# PAW4_NOMAG_Cheesecake-Blueberry-LSM6DSV_.net
KiCad netlist of a schematic drawn in EasyEDA Pro
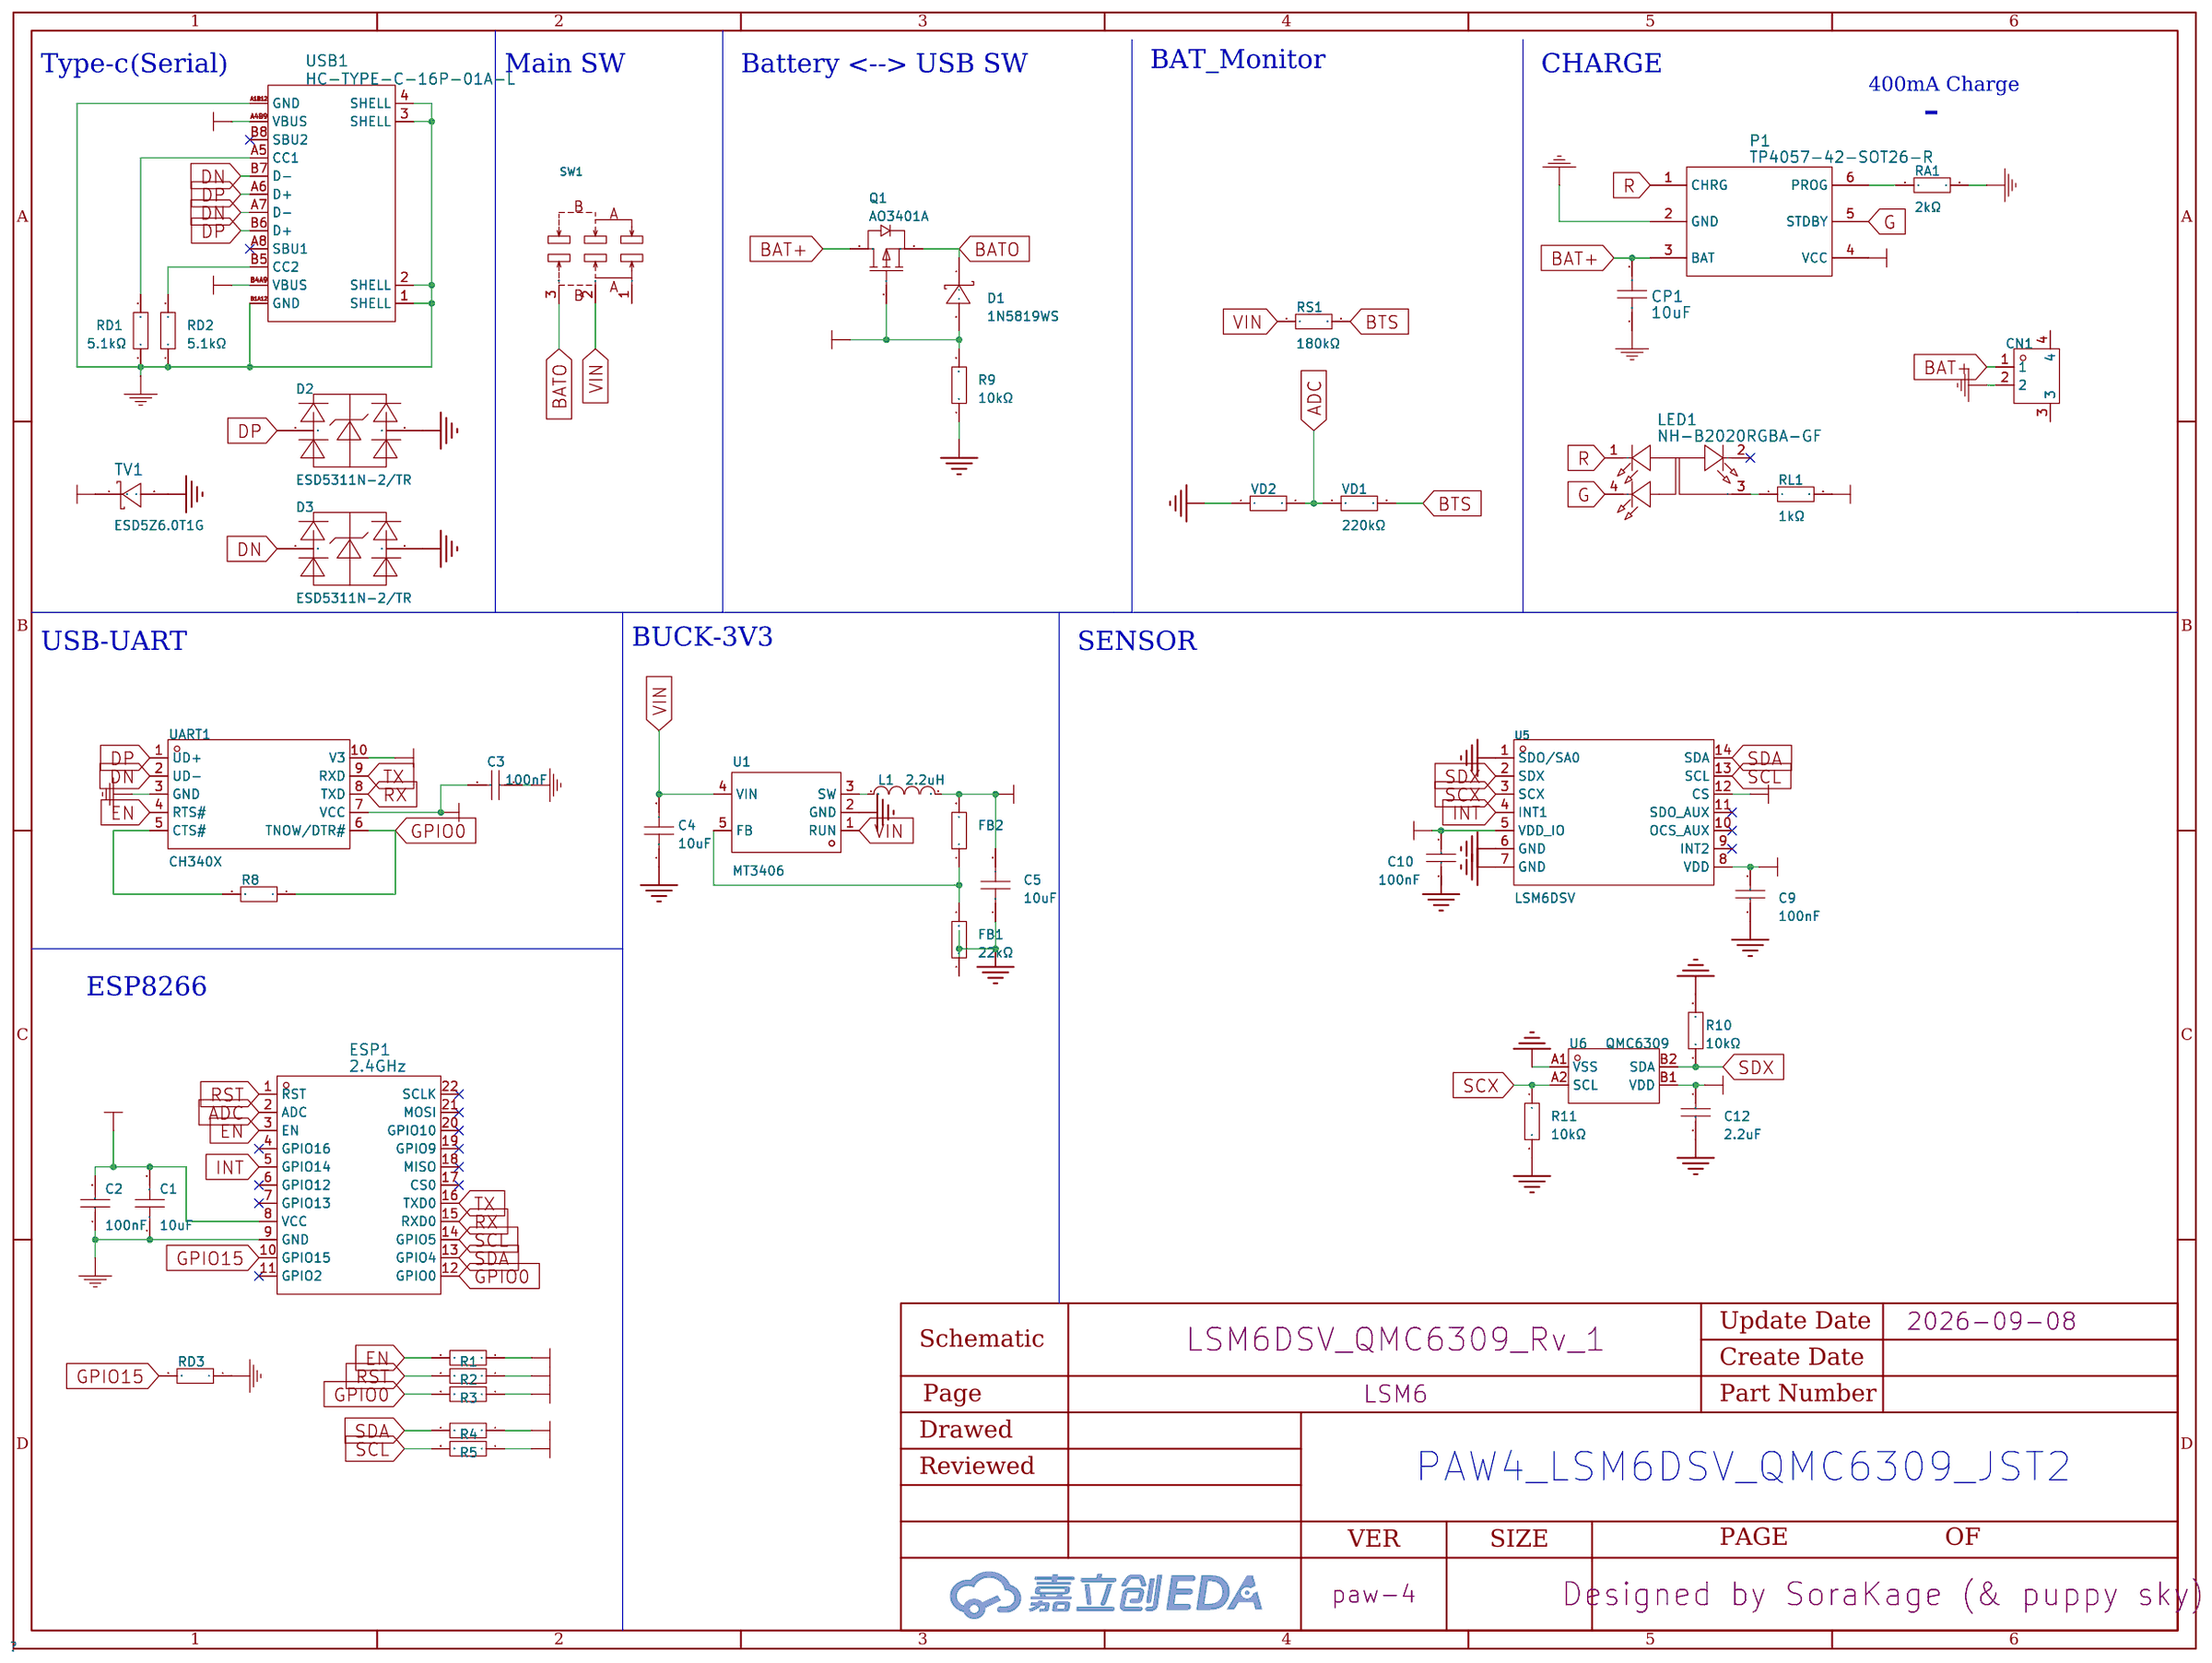
[diagram p0: schematic sheet]

(export (version "E")
  (design (tool "Eeschema 10.0.6"))
  (components
    (comp (ref "C1")
      (value "10uF")
      (footprint "easyedapro:C0402")
      (description "Capacitance:10uF Tolerance:±10% Tolerance:±10% Voltage Rating:10V Temperature Coefficient:X5R")
      (fields
        (field (name "Manufacturer Part") "CL10A106KP8NNNC")
        (field (name "Manufacturer") "SAMSUNG(三星)")
      )
      (libsource (lib "easyedapro") (part "CL05A105KA5NQNC"))
    )
    (comp (ref "C2")
      (value "100nF")
      (footprint "easyedapro:C0402")
      (description "容值:100nF;精度:±10%;额定电压:16V;材质(温度系数):X7R;")
      (fields
        (field (name "Manufacturer Part") "CL05B104KO5NNNC")
        (field (name "Manufacturer") "SAMSUNG(三星)")
      )
      (libsource (lib "easyedapro") (part "CL05B104KO5NNNC"))
    )
    (comp (ref "C3")
      (value "100nF")
      (footprint "easyedapro:C0402")
      (description "容值:100nF;精度:±10%;额定电压:16V;材质(温度系数):X7R;")
      (fields
        (field (name "Manufacturer Part") "CL05B104KO5NNNC")
        (field (name "Manufacturer") "SAMSUNG(三星)")
      )
      (libsource (lib "easyedapro") (part "CL05B104KO5NNNC"))
    )
    (comp (ref "C4")
      (value "10uF")
      (footprint "easyedapro:C0603")
      (description "容值:10uF;精度:±10%;额定电压:10V;材质(温度系数):X5R;")
      (fields
        (field (name "Manufacturer Part") "CL10A106KP8NNNC")
        (field (name "Manufacturer") "SAMSUNG(三星)")
      )
      (libsource (lib "easyedapro") (part "CL10A106KP8NNNC"))
    )
    (comp (ref "C5")
      (value "10uF")
      (footprint "easyedapro:C0603")
      (description "容值:10uF;精度:±10%;额定电压:10V;材质(温度系数):X5R;")
      (fields
        (field (name "Manufacturer Part") "CL10A106KP8NNNC")
        (field (name "Manufacturer") "SAMSUNG(三星)")
      )
      (libsource (lib "easyedapro") (part "CL10A106KP8NNNC"))
    )
    (comp (ref "C9")
      (value "100nF")
      (footprint "easyedapro:C0402")
      (description "容值:100nF;精度:±10%;额定电压:16V;材质(温度系数):X7R;")
      (fields
        (field (name "Manufacturer Part") "CL05B104KO5NNNC")
        (field (name "Manufacturer") "SAMSUNG(三星)")
      )
      (libsource (lib "easyedapro") (part "CL05B104KO5NNNC"))
    )
    (comp (ref "C10")
      (value "100nF")
      (footprint "easyedapro:C0402")
      (description "容值:100nF;精度:±10%;额定电压:16V;材质(温度系数):X7R;")
      (fields
        (field (name "Manufacturer Part") "CL05B104KO5NNNC")
        (field (name "Manufacturer") "SAMSUNG(三星)")
      )
      (libsource (lib "easyedapro") (part "CL05B104KO5NNNC"))
    )
    (comp (ref "C12")
      (value "2.2uF")
      (footprint "easyedapro:C0402")
      (description "Capacitance:2.2uF Tolerance:±10% Tolerance:±10% Voltage Rating:6.3V Temperature Coefficient:X5R")
      (fields (field (name "Manufacturer Part") "0402X225K6R3NT") (field (name "Manufacturer") "FH(风华)"))
      (libsource (lib "easyedapro") (part "CL05B104KO5NNNC"))
    )
    (comp (ref "CN1")
      (value "S2B-PH-SM4-TB(LF)(SN)")
      (footprint "easyedapro:CONN-SMD_P2.00_S2B-PH-SM4-TB-LF-SN")
      (fields (field (name "Manufacturer") "JST"))
      (libsource (lib "easyedapro") (part "S2B-PH-SM4-TB(LF)(SN)"))
    )
    (comp (ref "CP1")
      (value "10uF")
      (footprint "easyedapro:C0603")
      (fields
        (field (name "Manufacturer Part") "CL10A106KP8NNNC")
        (field (name "Manufacturer") "SAMSUNG(三星)")
      )
      (libsource (lib "easyedapro") (part "10uF"))
    )
    (comp (ref "D1")
      (value "1N5819WS")
      (footprint "easyedapro:SOD-323_L1.8-W1.3-LS2.5-RD")
      (description "直流反向耐压(Vr):40V;平均整流电流(Io):1A;正向压降(Vf):600mV@1A;")
      (fields (field (name "Manufacturer") "Hottech(合科泰)"))
      (libsource (lib "easyedapro") (part "1N5819WS"))
    )
    (comp (ref "D2")
      (value "ESD5311N-2/TR")
      (footprint "easyedapro:X1-DFN1006-2_L1.0-W0.6_ESD5311N-2-TR")
      (fields (field (name "Manufacturer") "WILLSEMI(韦尔)"))
      (libsource (lib "easyedapro") (part "ESD5311N-2/TR"))
    )
    (comp (ref "D3")
      (value "ESD5311N-2/TR")
      (footprint "easyedapro:X1-DFN1006-2_L1.0-W0.6_ESD5311N-2-TR")
      (fields (field (name "Manufacturer") "WILLSEMI(韦尔)"))
      (libsource (lib "easyedapro") (part "ESD5311N-2/TR"))
    )
    (comp (ref "ESP1")
      (value "2.4GHz")
      (description "核心处理器:ESP8266芯片;频率:2.4GHz;天线形式:板载PCB天线;发射功率:16dBm;接收灵敏度:-90dBm;")
      (fields
        (field (name "Manufacturer Part") "ESP-12F(ESP8266MOD)")
        (field (name "Manufacturer") "Ai-Thinker(安信可)")
      )
      (libsource (lib "easyedapro") (part "ESP-12F(ESP8266MOD)"))
    )
    (comp (ref "FB1")
      (value "22kΩ")
      (footprint "easyedapro:R0402")
      (description "电阻类型:厚膜电阻;阻值:22kΩ;精度:±1%;功率:62.5mW;")
      (fields
        (field (name "Manufacturer Part") "0402WGF2202TCE")
        (field (name "Manufacturer") "UNI-ROYAL(厚声)")
      )
      (libsource (lib "easyedapro") (part "0402WGF2202TCE"))
    )
    (comp (ref "FB2")
      (value "100kΩ")
      (footprint "easyedapro:R0402")
      (fields
        (field (name "Manufacturer Part") "0402WGF1003TCE")
        (field (name "Manufacturer") "UNI-ROYAL(厚声)")
      )
      (libsource (lib "easyedapro") (part "0402WGF1003TCE"))
    )
    (comp (ref "L1")
      (value "2.2uH")
      (footprint "easyedapro:IND-SMD_L2.5-W2.0_YXMBL252010P")
      (description "类型:一体成型电感;电感值:2.2uH;精度:±20%;额定电流:2.1A;饱和电流(Isat):3A;")
      (fields (field (name "Manufacturer Part") "APH252010T2R2M") (field (name "Manufacturer") "APV(爱普微)"))
      (libsource (lib "easyedapro") (part "APH252010T2R2M"))
    )
    (comp (ref "LED1")
      (value "NH-B2020RGBA-GF")
      (footprint "easyedapro:LED-ARRAY-SMD_4P-L2.1-W2.1-TL_NH-B2020RGBA")
      (fields (field (name "Manufacturer") "国星光电"))
      (libsource (lib "easyedapro") (part "NH-B2020RGBA-GF"))
    )
    (comp (ref "P1")
      (value "TP4057-42-SOT26-R")
      (footprint "easyedapro:SOT-23-6_L2.9-W1.6-P0.95-LS2.8-BL")
      (fields (field (name "Manufacturer") "TOPPOWER(南京拓微)"))
      (libsource (lib "easyedapro") (part "TP4057"))
    )
    (comp (ref "Q1")
      (value "AO3401A")
      (footprint "easyedapro:SOT-23_L2.9-W1.3-P1.90-LS2.4-BR")
      (description "类型:P沟道;漏源电压(Vdss):30V;连续漏极电流(Id):4A;功率(Pd):1.4W;导通电阻(RDS(on)@Vgs,Id):44mΩ@10V,4.3A;")
      (fields (field (name "Manufacturer") "AOS"))
      (libsource (lib "easyedapro") (part "AO3401A"))
    )
    (comp (ref "R1")
      (value "4.7kΩ")
      (footprint "easyedapro:R0402")
      (fields
        (field (name "Manufacturer Part") "0402WGF4701TCE")
        (field (name "Manufacturer") "UNI-ROYAL(厚声)")
      )
      (libsource (lib "easyedapro") (part "0402WGF4701TCE"))
    )
    (comp (ref "R2")
      (value "4.7kΩ")
      (footprint "easyedapro:R0402")
      (fields
        (field (name "Manufacturer Part") "0402WGF4701TCE")
        (field (name "Manufacturer") "UNI-ROYAL(厚声)")
      )
      (libsource (lib "easyedapro") (part "0402WGF4701TCE"))
    )
    (comp (ref "R3")
      (value "4.7kΩ")
      (footprint "easyedapro:R0402")
      (fields
        (field (name "Manufacturer Part") "0402WGF4701TCE")
        (field (name "Manufacturer") "UNI-ROYAL(厚声)")
      )
      (libsource (lib "easyedapro") (part "0402WGF4701TCE"))
    )
    (comp (ref "R4")
      (value "4.7kΩ")
      (footprint "easyedapro:R0402")
      (fields
        (field (name "Manufacturer Part") "0402WGF4701TCE")
        (field (name "Manufacturer") "UNI-ROYAL(厚声)")
      )
      (libsource (lib "easyedapro") (part "0402WGF4701TCE"))
    )
    (comp (ref "R5")
      (value "4.7kΩ")
      (footprint "easyedapro:R0402")
      (fields
        (field (name "Manufacturer Part") "0402WGF4701TCE")
        (field (name "Manufacturer") "UNI-ROYAL(厚声)")
      )
      (libsource (lib "easyedapro") (part "0402WGF4701TCE"))
    )
    (comp (ref "R8")
      (value "4.7kΩ")
      (footprint "easyedapro:R0402")
      (fields
        (field (name "Manufacturer Part") "0402WGF4701TCE")
        (field (name "Manufacturer") "UNI-ROYAL(厚声)")
      )
      (libsource (lib "easyedapro") (part "0402WGF4701TCE"))
    )
    (comp (ref "R9")
      (value "10kΩ")
      (footprint "easyedapro:R0402")
      (description "电阻类型:厚膜电阻;阻值:10kΩ;精度:±1%;功率:62.5mW;")
      (fields
        (field (name "Manufacturer Part") "0402WGF1002TCE")
        (field (name "Manufacturer") "UNI-ROYAL(厚声)")
      )
      (libsource (lib "easyedapro") (part "0402WGF1002TCE"))
    )
    (comp (ref "R10")
      (value "10kΩ")
      (footprint "easyedapro:R0402")
      (description "电阻类型:厚膜电阻;阻值:10kΩ;精度:±1%;功率:62.5mW;")
      (fields
        (field (name "Manufacturer Part") "0402WGF1002TCE")
        (field (name "Manufacturer") "UNI-ROYAL(厚声)")
      )
      (libsource (lib "easyedapro") (part "0402WGF1002TCE"))
    )
    (comp (ref "R11")
      (value "10kΩ")
      (footprint "easyedapro:R0402")
      (description "电阻类型:厚膜电阻;阻值:10kΩ;精度:±1%;功率:62.5mW;")
      (fields
        (field (name "Manufacturer Part") "0402WGF1002TCE")
        (field (name "Manufacturer") "UNI-ROYAL(厚声)")
      )
      (libsource (lib "easyedapro") (part "0402WGF1002TCE"))
    )
    (comp (ref "RA1")
      (value "2kΩ")
      (footprint "easyedapro:R0402")
      (description "电阻类型:厚膜电阻;阻值:2kΩ;精度:±1%;功率:62.5mW;")
      (fields
        (field (name "Manufacturer Part") "0402WGF2001TCE")
        (field (name "Manufacturer") "UNI-ROYAL(厚声)")
      )
      (libsource (lib "easyedapro") (part "0402WGF2001TCE"))
    )
    (comp (ref "RD1")
      (value "5.1kΩ")
      (footprint "easyedapro:R0402")
      (description "电阻类型:厚膜电阻;阻值:5.1kΩ;精度:±1%;功率:62.5mW;")
      (fields
        (field (name "Manufacturer Part") "0402WGF5101TCE")
        (field (name "Manufacturer") "UNI-ROYAL(厚声)")
      )
      (libsource (lib "easyedapro") (part "0402WGF5101TCE"))
    )
    (comp (ref "RD2")
      (value "5.1kΩ")
      (footprint "easyedapro:R0402")
      (description "电阻类型:厚膜电阻;阻值:5.1kΩ;精度:±1%;功率:62.5mW;")
      (fields
        (field (name "Manufacturer Part") "0402WGF5101TCE")
        (field (name "Manufacturer") "UNI-ROYAL(厚声)")
      )
      (libsource (lib "easyedapro") (part "0402WGF5101TCE"))
    )
    (comp (ref "RD3")
      (value "4.7kΩ")
      (footprint "easyedapro:R0402")
      (fields
        (field (name "Manufacturer Part") "0402WGF4701TCE")
        (field (name "Manufacturer") "UNI-ROYAL(厚声)")
      )
      (libsource (lib "easyedapro") (part "0402WGF4701TCE"))
    )
    (comp (ref "RL1")
      (value "1kΩ")
      (footprint "easyedapro:R0402")
      (description "电阻类型:厚膜电阻;阻值:1kΩ;精度:±1%;功率:62.5mW;")
      (fields
        (field (name "Manufacturer Part") "0402WGF1001TCE")
        (field (name "Manufacturer") "UNI-ROYAL(厚声)")
      )
      (libsource (lib "easyedapro") (part "0402WGF1001TCE"))
    )
    (comp (ref "RS1")
      (value "180kΩ")
      (footprint "easyedapro:R0402")
      (description "阻值:180kΩ;精度:±1%;功率:62.5mW;温度系数:±100ppm/°C;电阻类型:厚膜电阻;")
      (fields
        (field (name "Manufacturer Part") "0402WGF1803TCE")
        (field (name "Manufacturer") "UNI-ROYAL(厚声)")
      )
      (libsource (lib "easyedapro") (part "0402WGF1803TCE"))
    )
    (comp (ref "SW1")
      (value "K3-1280S-F1")
      (footprint "easyedapro:SW-SMD_K3-1280S-K1")
      (fields (field (name "Manufacturer") "韩国韩荣"))
      (libsource (lib "easyedapro") (part "K3-1280S-F2"))
    )
    (comp (ref "TV1")
      (value "ESD5Z6.0T1G")
      (footprint "easyedapro:SOD-523F_L1.2-W0.8-LS1.7-RD")
      (fields (field (name "Manufacturer") "onsemi(安森美)"))
      (libsource (lib "easyedapro") (part "ESD5Z6.0T1G"))
    )
    (comp (ref "U1")
      (value "MT3406")
      (footprint "easyedapro:SOT-23-5_L3.0-W1.7-P0.95-LS2.8-BR")
      (description "功能类型:降压型;同步整流:-;输出通道数:-;拓扑结构:-;输入电压:-;输出电流(最大值):-;开关频率:-;")
      (fields (field (name "Manufacturer") "西安航天民芯"))
      (libsource (lib "easyedapro") (part "M3406"))
    )
    (comp (ref "U5")
      (value "LSM6DSV")
      (footprint "easyedapro:LGA-14_L3.0-W2.5-P0.50-TL")
      (fields (field (name "Manufacturer") "ST(意法半导体)"))
      (libsource (lib "easyedapro") (part "LSM6DSVQTR"))
    )
    (comp (ref "U6")
      (value "QMC6309")
      (footprint "easyedapro:X1-WLB0808-4_L0.8-W0.8-P0.40-TL")
      (fields (field (name "Manufacturer") "QST(上海矽睿)"))
      (libsource (lib "easyedapro") (part "QMC6309"))
    )
    (comp (ref "UART1")
      (value "CH340X")
      (footprint "easyedapro:MSOP-10_L3.0-W3.0-P0.50-LS5.0-BL")
      (fields (field (name "Manufacturer") "WCH(南京沁恒)"))
      (libsource (lib "easyedapro") (part "CH340X"))
    )
    (comp (ref "USB1")
      (value "HC-TYPE-C-16P-01A-L")
      (footprint "easyedapro:USB-C-SMD_G-SWITCH_GT-USB-7010EN")
      (fields (field (name "Manufacturer") "HCTL(华灿天禄)"))
      (libsource (lib "easyedapro") (part "HC-TYPE-C-16P-01A-L"))
    )
    (comp (ref "VD1")
      (value "220kΩ")
      (footprint "easyedapro:R0402")
      (description "电阻类型:厚膜电阻;阻值:220kΩ;精度:±1%;功率:62.5mW;")
      (fields
        (field (name "Manufacturer Part") "0402WGF2203TCE")
        (field (name "Manufacturer") "UNI-ROYAL(厚声)")
      )
      (libsource (lib "easyedapro") (part "0402WGF2203TCE"))
    )
    (comp (ref "VD2")
      (value "100kΩ")
      (footprint "easyedapro:R0402")
      (fields
        (field (name "Manufacturer Part") "0402WGF1003TCE")
        (field (name "Manufacturer") "UNI-ROYAL(厚声)")
      )
      (libsource (lib "easyedapro") (part "0402WGF1003TCE"))
    )
  )
  (nets
    (net (code "1") (name "+5V") (class "Default")
      (node (ref "D1") (pin "2") (pinfunction "A_2") (pintype "unspecified"))
      (node (ref "P1") (pin "4") (pinfunction "VCC_4") (pintype "unspecified"))
      (node (ref "Q1") (pin "1") (pinfunction "G_1") (pintype "input"))
      (node (ref "R9") (pin "2") (pinfunction "2_2") (pintype "input"))
      (node (ref "RL1") (pin "2") (pinfunction "2_2") (pintype "input"))
      (node (ref "TV1") (pin "1") (pinfunction "K_1") (pintype "input"))
      (node (ref "USB1") (pin "A4B9") (pinfunction "VBUS_A4B9") (pintype "unspecified"))
      (node (ref "USB1") (pin "B4A9") (pinfunction "VBUS_B4A9") (pintype "unspecified"))
    )
    (net (code "2") (name "3V3") (class "Default")
      (node (ref "C1") (pin "2") (pinfunction "2_2") (pintype "unspecified"))
      (node (ref "C10") (pin "1") (pinfunction "1_1") (pintype "input"))
      (node (ref "C12") (pin "2") (pinfunction "2_2") (pintype "input"))
      (node (ref "C2") (pin "2") (pinfunction "2_2") (pintype "input"))
      (node (ref "C3") (pin "2") (pinfunction "2_2") (pintype "input"))
      (node (ref "C5") (pin "2") (pinfunction "2_2") (pintype "unspecified"))
      (node (ref "C9") (pin "1") (pinfunction "1_1") (pintype "input"))
      (node (ref "ESP1") (pin "8") (pinfunction "VCC_8") (pintype "input"))
      (node (ref "FB2") (pin "2") (pinfunction "2_2") (pintype "input"))
      (node (ref "L1") (pin "2") (pinfunction "2_2") (pintype "unspecified"))
      (node (ref "R1") (pin "1") (pinfunction "1_1") (pintype "input"))
      (node (ref "R2") (pin "1") (pinfunction "1_1") (pintype "input"))
      (node (ref "R3") (pin "1") (pinfunction "1_1") (pintype "input"))
      (node (ref "R4") (pin "1") (pinfunction "1_1") (pintype "input"))
      (node (ref "R5") (pin "1") (pinfunction "1_1") (pintype "input"))
      (node (ref "U5") (pin "12") (pinfunction "CS_12") (pintype "unspecified"))
      (node (ref "U5") (pin "5") (pinfunction "VDD_IO_5") (pintype "unspecified"))
      (node (ref "U5") (pin "8") (pinfunction "VDD_8") (pintype "unspecified"))
      (node (ref "U6") (pin "B1") (pinfunction "VDD_B1") (pintype "unspecified"))
      (node (ref "UART1") (pin "10") (pinfunction "V3_10") (pintype "unspecified"))
      (node (ref "UART1") (pin "7") (pinfunction "VCC_7") (pintype "unspecified"))
    )
    (net (code "3") (name "ADC") (class "Default")
      (node (ref "ESP1") (pin "2") (pinfunction "ADC_2") (pintype "input"))
      (node (ref "VD1") (pin "1") (pinfunction "1_1") (pintype "input"))
      (node (ref "VD2") (pin "2") (pinfunction "2_2") (pintype "input"))
    )
    (net (code "4") (name "BAT+") (class "Default")
      (node (ref "CN1") (pin "1") (pinfunction "1_1") (pintype "unspecified"))
      (node (ref "CP1") (pin "2") (pinfunction "2_2") (pintype "input"))
      (node (ref "P1") (pin "3") (pinfunction "BAT_3") (pintype "unspecified"))
      (node (ref "Q1") (pin "3") (pinfunction "D_3") (pintype "input"))
    )
    (net (code "5") (name "BATO") (class "Default")
      (node (ref "D1") (pin "1") (pinfunction "K_1") (pintype "unspecified"))
      (node (ref "Q1") (pin "2") (pinfunction "S_2") (pintype "input"))
      (node (ref "SW1") (pin "3") (pinfunction "3_3") (pintype "unspecified"))
    )
    (net (code "6") (name "BTS") (class "Default")
      (node (ref "RS1") (pin "2") (pinfunction "2_2") (pintype "input"))
      (node (ref "VD1") (pin "2") (pinfunction "2_2") (pintype "input"))
    )
    (net (code "7") (name "DN") (class "Default")
      (node (ref "D3") (pin "1") (pinfunction "1_1") (pintype "unspecified"))
      (node (ref "UART1") (pin "2") (pinfunction "UD-_2") (pintype "unspecified"))
      (node (ref "USB1") (pin "A7") (pinfunction "D-_A7") (pintype "unspecified"))
      (node (ref "USB1") (pin "B7") (pinfunction "D-_B7") (pintype "unspecified"))
    )
    (net (code "8") (name "DP") (class "Default")
      (node (ref "D2") (pin "1") (pinfunction "1_1") (pintype "unspecified"))
      (node (ref "UART1") (pin "1") (pinfunction "UD+_1") (pintype "unspecified"))
      (node (ref "USB1") (pin "A6") (pinfunction "D+_A6") (pintype "unspecified"))
      (node (ref "USB1") (pin "B6") (pinfunction "D+_B6") (pintype "unspecified"))
    )
    (net (code "9") (name "EN") (class "Default")
      (node (ref "ESP1") (pin "3") (pinfunction "EN_3") (pintype "input"))
      (node (ref "R1") (pin "2") (pinfunction "2_2") (pintype "input"))
      (node (ref "UART1") (pin "4") (pinfunction "RTS#_4") (pintype "unspecified"))
    )
    (net (code "10") (name "G") (class "Default")
      (node (ref "LED1") (pin "4") (pinfunction "-_4") (pintype "unspecified"))
      (node (ref "P1") (pin "5") (pinfunction "STDBY_5") (pintype "unspecified"))
    )
    (net (code "11") (name "GND") (class "Default")
      (node (ref "C1") (pin "1") (pinfunction "1_1") (pintype "unspecified"))
      (node (ref "C10") (pin "2") (pinfunction "2_2") (pintype "input"))
      (node (ref "C12") (pin "1") (pinfunction "1_1") (pintype "input"))
      (node (ref "C2") (pin "1") (pinfunction "1_1") (pintype "input"))
      (node (ref "C3") (pin "1") (pinfunction "1_1") (pintype "input"))
      (node (ref "C4") (pin "1") (pinfunction "1_1") (pintype "unspecified"))
      (node (ref "C5") (pin "1") (pinfunction "1_1") (pintype "unspecified"))
      (node (ref "C9") (pin "2") (pinfunction "2_2") (pintype "input"))
      (node (ref "CN1") (pin "2") (pinfunction "2_2") (pintype "unspecified"))
      (node (ref "CP1") (pin "1") (pinfunction "1_1") (pintype "input"))
      (node (ref "D2") (pin "2") (pinfunction "2_2") (pintype "unspecified"))
      (node (ref "D3") (pin "2") (pinfunction "2_2") (pintype "unspecified"))
      (node (ref "ESP1") (pin "9") (pinfunction "GND_9") (pintype "input"))
      (node (ref "FB1") (pin "1") (pinfunction "1_1") (pintype "input"))
      (node (ref "P1") (pin "2") (pinfunction "GND_2") (pintype "unspecified"))
      (node (ref "R10") (pin "2") (pinfunction "2_2") (pintype "input"))
      (node (ref "R11") (pin "2") (pinfunction "2_2") (pintype "input"))
      (node (ref "R9") (pin "1") (pinfunction "1_1") (pintype "input"))
      (node (ref "RA1") (pin "2") (pinfunction "2_2") (pintype "input"))
      (node (ref "RD1") (pin "1") (pinfunction "1_1") (pintype "input"))
      (node (ref "RD2") (pin "1") (pinfunction "1_1") (pintype "input"))
      (node (ref "RD3") (pin "1") (pinfunction "1_1") (pintype "input"))
      (node (ref "TV1") (pin "2") (pinfunction "A_2") (pintype "input"))
      (node (ref "U1") (pin "2") (pinfunction "GND_2") (pintype "input"))
      (node (ref "U5") (pin "1") (pinfunction "SDO/SA0_1") (pintype "unspecified"))
      (node (ref "U5") (pin "6") (pinfunction "GND_6") (pintype "unspecified"))
      (node (ref "U5") (pin "7") (pinfunction "GND_7") (pintype "unspecified"))
      (node (ref "U6") (pin "A1") (pinfunction "VSS_A1") (pintype "unspecified"))
      (node (ref "UART1") (pin "3") (pinfunction "GND_3") (pintype "unspecified"))
      (node (ref "USB1") (pin "1") (pinfunction "SHELL_1") (pintype "unspecified"))
      (node (ref "USB1") (pin "2") (pinfunction "SHELL_2") (pintype "unspecified"))
      (node (ref "USB1") (pin "3") (pinfunction "SHELL_3") (pintype "unspecified"))
      (node (ref "USB1") (pin "4") (pinfunction "SHELL_4") (pintype "unspecified"))
      (node (ref "USB1") (pin "A1B12") (pinfunction "GND_A1B12") (pintype "unspecified"))
      (node (ref "USB1") (pin "B1A12") (pinfunction "GND_B1A12") (pintype "unspecified"))
      (node (ref "VD2") (pin "1") (pinfunction "1_1") (pintype "input"))
    )
    (net (code "12") (name "GPIO0") (class "Default")
      (node (ref "ESP1") (pin "12") (pinfunction "GPIO0_12") (pintype "input"))
      (node (ref "R3") (pin "2") (pinfunction "2_2") (pintype "input"))
      (node (ref "R8") (pin "1") (pinfunction "1_1") (pintype "input"))
      (node (ref "UART1") (pin "6") (pinfunction "TNOW/DTR#_6") (pintype "unspecified"))
    )
    (net (code "13") (name "GPIO15") (class "Default")
      (node (ref "ESP1") (pin "10") (pinfunction "GPIO15_10") (pintype "input"))
      (node (ref "RD3") (pin "2") (pinfunction "2_2") (pintype "input"))
    )
    (net (code "14") (name "INT") (class "Default")
      (node (ref "ESP1") (pin "5") (pinfunction "GPIO14_5") (pintype "input"))
      (node (ref "U5") (pin "4") (pinfunction "INT1_4") (pintype "unspecified"))
    )
    (net (code "15") (name "Net-(LED1-+)") (class "Default")
      (node (ref "LED1") (pin "3") (pinfunction "+_3") (pintype "unspecified"))
      (node (ref "RL1") (pin "1") (pinfunction "1_1") (pintype "input"))
    )
    (net (code "16") (name "Net-(P1-PROG)") (class "Default")
      (node (ref "P1") (pin "6") (pinfunction "PROG_6") (pintype "unspecified"))
      (node (ref "RA1") (pin "1") (pinfunction "1_1") (pintype "input"))
    )
    (net (code "17") (name "Net-(U1-FB)") (class "Default")
      (node (ref "FB1") (pin "2") (pinfunction "2_2") (pintype "input"))
      (node (ref "FB2") (pin "1") (pinfunction "1_1") (pintype "input"))
      (node (ref "U1") (pin "5") (pinfunction "FB_5") (pintype "input"))
    )
    (net (code "18") (name "Net-(U1-SW)") (class "Default")
      (node (ref "L1") (pin "1") (pinfunction "1_1") (pintype "unspecified"))
      (node (ref "U1") (pin "3") (pinfunction "SW_3") (pintype "input"))
    )
    (net (code "19") (name "Net-(UART1-CTS#)") (class "Default")
      (node (ref "R8") (pin "2") (pinfunction "2_2") (pintype "input"))
      (node (ref "UART1") (pin "5") (pinfunction "CTS#_5") (pintype "unspecified"))
    )
    (net (code "20") (name "Net-(USB1-CC1)") (class "Default")
      (node (ref "RD1") (pin "2") (pinfunction "2_2") (pintype "input"))
      (node (ref "USB1") (pin "A5") (pinfunction "CC1_A5") (pintype "unspecified"))
    )
    (net (code "21") (name "Net-(USB1-CC2)") (class "Default")
      (node (ref "RD2") (pin "2") (pinfunction "2_2") (pintype "input"))
      (node (ref "USB1") (pin "B5") (pinfunction "CC2_B5") (pintype "unspecified"))
    )
    (net (code "22") (name "R") (class "Default")
      (node (ref "LED1") (pin "1") (pinfunction "-_1") (pintype "unspecified"))
      (node (ref "P1") (pin "1") (pinfunction "CHRG_1") (pintype "unspecified"))
    )
    (net (code "23") (name "RST") (class "Default")
      (node (ref "ESP1") (pin "1") (pinfunction "RST_1") (pintype "input"))
      (node (ref "R2") (pin "2") (pinfunction "2_2") (pintype "input"))
    )
    (net (code "24") (name "RX") (class "Default")
      (node (ref "ESP1") (pin "15") (pinfunction "RXD0_15") (pintype "input"))
      (node (ref "UART1") (pin "8") (pinfunction "TXD_8") (pintype "unspecified"))
    )
    (net (code "25") (name "SCL") (class "Default")
      (node (ref "ESP1") (pin "14") (pinfunction "GPIO5_14") (pintype "input"))
      (node (ref "R5") (pin "2") (pinfunction "2_2") (pintype "input"))
      (node (ref "U5") (pin "13") (pinfunction "SCL_13") (pintype "unspecified"))
    )
    (net (code "26") (name "SCX") (class "Default")
      (node (ref "R11") (pin "1") (pinfunction "1_1") (pintype "input"))
      (node (ref "U5") (pin "3") (pinfunction "SCX_3") (pintype "unspecified"))
      (node (ref "U6") (pin "A2") (pinfunction "SCL_A2") (pintype "unspecified"))
    )
    (net (code "27") (name "SDA") (class "Default")
      (node (ref "ESP1") (pin "13") (pinfunction "GPIO4_13") (pintype "input"))
      (node (ref "R4") (pin "2") (pinfunction "2_2") (pintype "input"))
      (node (ref "U5") (pin "14") (pinfunction "SDA_14") (pintype "unspecified"))
    )
    (net (code "28") (name "SDX") (class "Default")
      (node (ref "R10") (pin "1") (pinfunction "1_1") (pintype "input"))
      (node (ref "U5") (pin "2") (pinfunction "SDX_2") (pintype "unspecified"))
      (node (ref "U6") (pin "B2") (pinfunction "SDA_B2") (pintype "unspecified"))
    )
    (net (code "29") (name "TX") (class "Default")
      (node (ref "ESP1") (pin "16") (pinfunction "TXD0_16") (pintype "input"))
      (node (ref "UART1") (pin "9") (pinfunction "RXD_9") (pintype "unspecified"))
    )
    (net (code "30") (name "VIN") (class "Default")
      (node (ref "C4") (pin "2") (pinfunction "2_2") (pintype "unspecified"))
      (node (ref "RS1") (pin "1") (pinfunction "1_1") (pintype "input"))
      (node (ref "SW1") (pin "2") (pinfunction "2_2") (pintype "unspecified"))
      (node (ref "U1") (pin "1") (pinfunction "RUN_1") (pintype "input"))
      (node (ref "U1") (pin "4") (pinfunction "VIN_4") (pintype "input"))
    )
    (net (code "31") (name "unconnected-(CN1-Pad3)") (class "Default")
      (node (ref "CN1") (pin "3") (pinfunction "3_3") (pintype "unspecified"))
    )
    (net (code "32") (name "unconnected-(CN1-Pad4)") (class "Default")
      (node (ref "CN1") (pin "4") (pinfunction "4_4") (pintype "unspecified"))
    )
    (net (code "33") (name "unconnected-(ESP1-CS0-Pad17)") (class "Default")
      (node (ref "ESP1") (pin "17") (pinfunction "CS0_17") (pintype "input+no_connect"))
    )
    (net (code "34") (name "unconnected-(ESP1-GPIO2-Pad11)") (class "Default")
      (node (ref "ESP1") (pin "11") (pinfunction "GPIO2_11") (pintype "input+no_connect"))
    )
    (net (code "35") (name "unconnected-(ESP1-GPIO9-Pad19)") (class "Default")
      (node (ref "ESP1") (pin "19") (pinfunction "GPIO9_19") (pintype "input+no_connect"))
    )
    (net (code "36") (name "unconnected-(ESP1-GPIO10-Pad20)") (class "Default")
      (node (ref "ESP1") (pin "20") (pinfunction "GPIO10_20") (pintype "input+no_connect"))
    )
    (net (code "37") (name "unconnected-(ESP1-GPIO12-Pad6)") (class "Default")
      (node (ref "ESP1") (pin "6") (pinfunction "GPIO12_6") (pintype "input+no_connect"))
    )
    (net (code "38") (name "unconnected-(ESP1-GPIO13-Pad7)") (class "Default")
      (node (ref "ESP1") (pin "7") (pinfunction "GPIO13_7") (pintype "input+no_connect"))
    )
    (net (code "39") (name "unconnected-(ESP1-GPIO16-Pad4)") (class "Default")
      (node (ref "ESP1") (pin "4") (pinfunction "GPIO16_4") (pintype "input+no_connect"))
    )
    (net (code "40") (name "unconnected-(ESP1-MISO-Pad18)") (class "Default")
      (node (ref "ESP1") (pin "18") (pinfunction "MISO_18") (pintype "input+no_connect"))
    )
    (net (code "41") (name "unconnected-(ESP1-MOSI-Pad21)") (class "Default")
      (node (ref "ESP1") (pin "21") (pinfunction "MOSI_21") (pintype "input+no_connect"))
    )
    (net (code "42") (name "unconnected-(ESP1-SCLK-Pad22)") (class "Default")
      (node (ref "ESP1") (pin "22") (pinfunction "SCLK_22") (pintype "input+no_connect"))
    )
    (net (code "43") (name "unconnected-(LED1---Pad2)") (class "Default")
      (node (ref "LED1") (pin "2") (pinfunction "-_2") (pintype "unspecified+no_connect"))
    )
    (net (code "44") (name "unconnected-(SW1-Pad1)") (class "Default")
      (node (ref "SW1") (pin "1") (pinfunction "1_1") (pintype "unspecified"))
    )
    (net (code "45") (name "unconnected-(U5-INT2-Pad9)") (class "Default")
      (node (ref "U5") (pin "9") (pinfunction "INT2_9") (pintype "unspecified+no_connect"))
    )
    (net (code "46") (name "unconnected-(U5-OCS_AUX-Pad10)") (class "Default")
      (node (ref "U5") (pin "10") (pinfunction "OCS_AUX_10") (pintype "unspecified+no_connect"))
    )
    (net (code "47") (name "unconnected-(U5-SDO_AUX-Pad11)") (class "Default")
      (node (ref "U5") (pin "11") (pinfunction "SDO_AUX_11") (pintype "unspecified+no_connect"))
    )
    (net (code "48") (name "unconnected-(USB1-SBU1-PadA8)") (class "Default")
      (node (ref "USB1") (pin "A8") (pinfunction "SBU1_A8") (pintype "unspecified+no_connect"))
    )
    (net (code "49") (name "unconnected-(USB1-SBU2-PadB8)") (class "Default")
      (node (ref "USB1") (pin "B8") (pinfunction "SBU2_B8") (pintype "unspecified+no_connect"))
    )
  )
)
